# POWER_5_0V_6A.net
KiCad netlist of a schematic drawn in Altium Designer
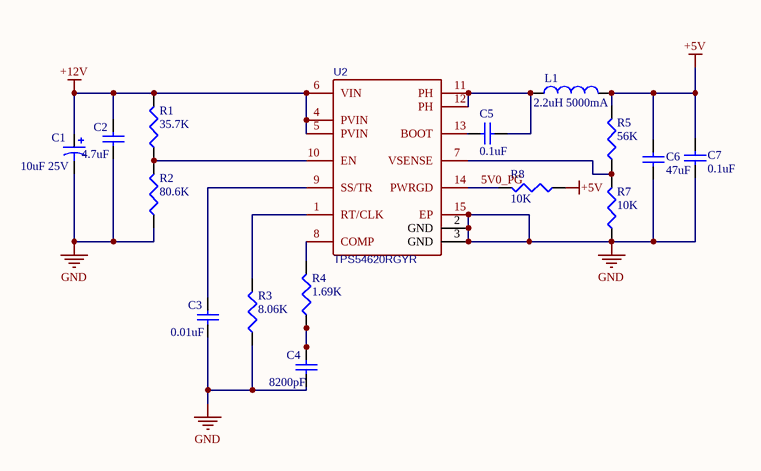
[diagram p0: POWER_5.0V_6A.SchDoc]

(export (version "E")
  (design (tool "Eeschema 10.0.6"))
  (components
    (comp (ref "C1")
      (value "10uF 25V")
      (footprint "47UF_16V")
      (description "Polarized Capacitor (Radial)")
      (fields (field (name "Comment") "Cap Pol1") (field (name "PUBLISHER") "Altium Limited"))
      (libsource (lib "Miscellaneous Devices") (part "Cap Pol1"))
    )
    (comp (ref "C2")
      (value "4.7uF")
      (footprint "C1210")
      (description "Capacitor (Semiconductor SIM Model)")
      (fields (field (name "Comment") "Cap Semi") (field (name "PUBLISHER") "Altium Limited"))
      (libsource (lib "Miscellaneous Devices") (part "Cap Semi"))
    )
    (comp (ref "C3")
      (value "0.01uF")
      (footprint "C1210")
      (description "Capacitor (Semiconductor SIM Model)")
      (fields (field (name "Comment") "Cap Semi") (field (name "PUBLISHER") "Altium Limited"))
      (libsource (lib "Miscellaneous Devices") (part "Cap Semi"))
    )
    (comp (ref "C4")
      (value "8200pF")
      (footprint "C1210")
      (description "Capacitor (Semiconductor SIM Model)")
      (fields (field (name "Comment") "Cap Semi") (field (name "PUBLISHER") "Altium Limited"))
      (libsource (lib "Miscellaneous Devices") (part "Cap Semi"))
    )
    (comp (ref "C5")
      (value "0.1uF")
      (footprint "C1210")
      (description "Capacitor (Semiconductor SIM Model)")
      (fields (field (name "Comment") "Cap Semi") (field (name "PUBLISHER") "Altium Limited"))
      (libsource (lib "Miscellaneous Devices") (part "Cap Semi"))
    )
    (comp (ref "C6")
      (value "47uF")
      (footprint "C1210")
      (description "Capacitor (Semiconductor SIM Model)")
      (fields (field (name "Comment") "Cap Semi") (field (name "PUBLISHER") "Altium Limited"))
      (libsource (lib "Miscellaneous Devices") (part "Cap Semi"))
    )
    (comp (ref "C7")
      (value "0.1uF")
      (footprint "C1210")
      (description "Capacitor (Semiconductor SIM Model)")
      (fields (field (name "Comment") "Cap Semi") (field (name "PUBLISHER") "Altium Limited"))
      (libsource (lib "Miscellaneous Devices") (part "Cap Semi"))
    )
    (comp (ref "L1")
      (value "2.2uH 5000mA")
      (footprint "IND-SMD_L5.5-W5.2")
      (description "Inductor")
      (fields (field (name "PUBLISHER") "Altium Limited"))
      (libsource (lib "Miscellaneous Devices") (part "Inductor"))
    )
    (comp (ref "R1")
      (value "35.7K")
      (footprint "J1-0603")
      (description "Resistor")
      (fields (field (name "Comment") "Res3") (field (name "PUBLISHER") "Altium Limited"))
      (libsource (lib "Miscellaneous Devices") (part "Res3"))
    )
    (comp (ref "R2")
      (value "80.6K")
      (footprint "J1-0603")
      (description "Resistor")
      (fields (field (name "Comment") "Res3") (field (name "PUBLISHER") "Altium Limited"))
      (libsource (lib "Miscellaneous Devices") (part "Res3"))
    )
    (comp (ref "R3")
      (value "8.06K")
      (footprint "J1-0603")
      (description "Resistor")
      (fields (field (name "Comment") "Res3") (field (name "PUBLISHER") "Altium Limited"))
      (libsource (lib "Miscellaneous Devices") (part "Res3"))
    )
    (comp (ref "R4")
      (value "1.69K")
      (footprint "J1-0603")
      (description "Resistor")
      (fields (field (name "Comment") "Res3") (field (name "PUBLISHER") "Altium Limited"))
      (libsource (lib "Miscellaneous Devices") (part "Res3"))
    )
    (comp (ref "R5")
      (value "56K")
      (footprint "J1-0603")
      (description "Resistor")
      (fields (field (name "Comment") "Res3") (field (name "PUBLISHER") "Altium Limited"))
      (libsource (lib "Miscellaneous Devices") (part "Res3"))
    )
    (comp (ref "R7")
      (value "10K")
      (footprint "J1-0603")
      (description "Resistor")
      (fields (field (name "Comment") "Res3") (field (name "PUBLISHER") "Altium Limited"))
      (libsource (lib "Miscellaneous Devices") (part "Res3"))
    )
    (comp (ref "R8")
      (value "10K")
      (footprint "J1-0603")
      (description "Resistor")
      (fields (field (name "Comment") "Res3") (field (name "PUBLISHER") "Altium Limited"))
      (libsource (lib "Miscellaneous Devices") (part "Res3"))
    )
    (comp (ref "U2")
      (value "TPS54620RGYR")
      (footprint "VQFN-14_L3.5-W3.5-P0.50-TL-EP_TPS54622RHLT")
      (fields (field (name "BOM_SUPPLIER PART") "C29438"))
      (libsource (lib "power_chip") (part "TPS54620RGYR"))
    )
  )
  (nets
    (net (code "1") (name "+5V") (class "Default")
      (node (ref "C6") (pin "1") (pinfunction "1_1") (pintype "passive"))
      (node (ref "C7") (pin "1") (pinfunction "1_1") (pintype "passive"))
      (node (ref "L1") (pin "2") (pinfunction "2_2") (pintype "passive"))
      (node (ref "R5") (pin "2") (pinfunction "2_2") (pintype "passive"))
      (node (ref "R8") (pin "1") (pinfunction "1_1") (pintype "passive"))
    )
    (net (code "2") (name "+12V") (class "Default")
      (node (ref "C1") (pin "1") (pinfunction "1_1") (pintype "passive"))
      (node (ref "C2") (pin "2") (pinfunction "2_2") (pintype "passive"))
      (node (ref "R1") (pin "2") (pinfunction "2_2") (pintype "passive"))
      (node (ref "U2") (pin "4") (pinfunction "PVIN_4") (pintype "passive"))
      (node (ref "U2") (pin "5") (pinfunction "PVIN_5") (pintype "passive"))
      (node (ref "U2") (pin "6") (pinfunction "VIN_6") (pintype "passive"))
    )
    (net (code "3") (name "/5V0_PG") (class "Default")
      (node (ref "R8") (pin "2") (pinfunction "2_2") (pintype "passive"))
      (node (ref "U2") (pin "14") (pinfunction "PWRGD_14") (pintype "passive"))
    )
    (net (code "4") (name "GND") (class "Default")
      (node (ref "C1") (pin "2") (pinfunction "2_2") (pintype "passive"))
      (node (ref "C2") (pin "1") (pinfunction "1_1") (pintype "passive"))
      (node (ref "C3") (pin "1") (pinfunction "1_1") (pintype "passive"))
      (node (ref "C4") (pin "1") (pinfunction "1_1") (pintype "passive"))
      (node (ref "C6") (pin "2") (pinfunction "2_2") (pintype "passive"))
      (node (ref "C7") (pin "2") (pinfunction "2_2") (pintype "passive"))
      (node (ref "R2") (pin "1") (pinfunction "1_1") (pintype "passive"))
      (node (ref "R3") (pin "1") (pinfunction "1_1") (pintype "passive"))
      (node (ref "R7") (pin "1") (pinfunction "1_1") (pintype "passive"))
      (node (ref "U2") (pin "15") (pinfunction "EP_15") (pintype "passive"))
      (node (ref "U2") (pin "2") (pinfunction "GND_2") (pintype "passive"))
      (node (ref "U2") (pin "3") (pinfunction "GND_3") (pintype "passive"))
    )
    (net (code "5") (name "Net-(C4-Pad2)") (class "Default")
      (node (ref "C4") (pin "2") (pinfunction "2_2") (pintype "passive"))
      (node (ref "R4") (pin "1") (pinfunction "1_1") (pintype "passive"))
    )
    (net (code "6") (name "Net-(C5-Pad1)") (class "Default")
      (node (ref "C5") (pin "1") (pinfunction "1_1") (pintype "passive"))
      (node (ref "L1") (pin "1") (pinfunction "1_1") (pintype "passive"))
      (node (ref "U2") (pin "11") (pinfunction "PH_11") (pintype "passive"))
      (node (ref "U2") (pin "12") (pinfunction "PH_12") (pintype "passive"))
    )
    (net (code "7") (name "Net-(U2-BOOT)") (class "Default")
      (node (ref "C5") (pin "2") (pinfunction "2_2") (pintype "passive"))
      (node (ref "U2") (pin "13") (pinfunction "BOOT_13") (pintype "passive"))
    )
    (net (code "8") (name "Net-(U2-COMP)") (class "Default")
      (node (ref "R4") (pin "2") (pinfunction "2_2") (pintype "passive"))
      (node (ref "U2") (pin "8") (pinfunction "COMP_8") (pintype "passive"))
    )
    (net (code "9") (name "Net-(U2-EN)") (class "Default")
      (node (ref "R1") (pin "1") (pinfunction "1_1") (pintype "passive"))
      (node (ref "R2") (pin "2") (pinfunction "2_2") (pintype "passive"))
      (node (ref "U2") (pin "10") (pinfunction "EN_10") (pintype "passive"))
    )
    (net (code "10") (name "Net-(U2-RT{slash}CLK)") (class "Default")
      (node (ref "R3") (pin "2") (pinfunction "2_2") (pintype "passive"))
      (node (ref "U2") (pin "1") (pinfunction "RT/CLK_1") (pintype "passive"))
    )
    (net (code "11") (name "Net-(U2-SS{slash}TR)") (class "Default")
      (node (ref "C3") (pin "2") (pinfunction "2_2") (pintype "passive"))
      (node (ref "U2") (pin "9") (pinfunction "SS/TR_9") (pintype "passive"))
    )
    (net (code "12") (name "Net-(U2-VSENSE)") (class "Default")
      (node (ref "R5") (pin "1") (pinfunction "1_1") (pintype "passive"))
      (node (ref "R7") (pin "2") (pinfunction "2_2") (pintype "passive"))
      (node (ref "U2") (pin "7") (pinfunction "VSENSE_7") (pintype "passive"))
    )
  )
)
